# 01_-_Power.net
KiCad netlist of a schematic drawn in Altium Designer
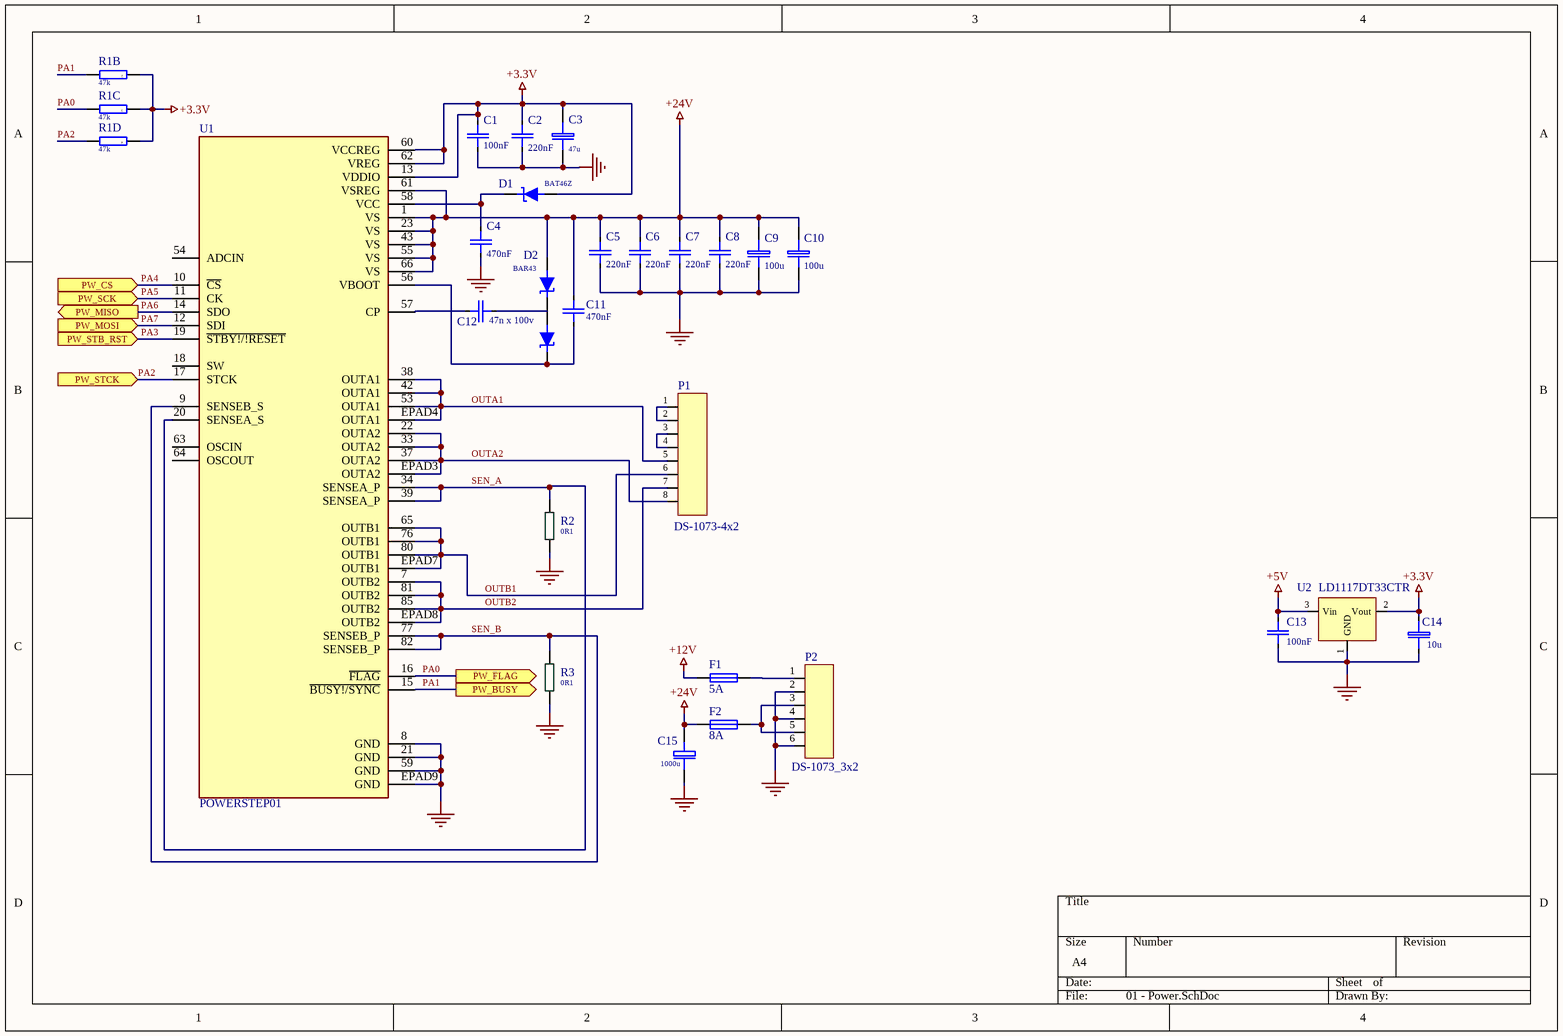
[diagram p0: 01 - Power.SchDoc]

(export (version "E")
  (design (tool "Eeschema 10.0.6"))
  (components
    (comp (ref "C1")
      (value "100nF")
      (footprint "CAP: 0805")
      (description "SMD-0805")
      (libsource (lib "RCL_SMD_Integrated_Library") (part "C-0805"))
    )
    (comp (ref "C2")
      (value "220nF")
      (footprint "CAP: 0805")
      (description "SMD-0805")
      (libsource (lib "RCL_SMD_Integrated_Library") (part "C-0805"))
    )
    (comp (ref "C3")
      (value "47u")
      (footprint "EL SMD Case C D5x5.3 h5.4(0505)")
      (description "EL 50V SMD Case C D5x5.3 h5.4")
      (libsource (lib "SMD-RCL") (part "EL 10u/50V"))
    )
    (comp (ref "C4")
      (value "470nF")
      (footprint "CAP: 0805")
      (description "SMD-0805")
      (libsource (lib "RCL_SMD_Integrated_Library") (part "C-0805"))
    )
    (comp (ref "C5")
      (value "220nF")
      (footprint "CAP: 0805")
      (description "SMD-0805")
      (libsource (lib "RCL_SMD_Integrated_Library") (part "C-0805"))
    )
    (comp (ref "C6")
      (value "220nF")
      (footprint "CAP: 0805")
      (description "SMD-0805")
      (libsource (lib "RCL_SMD_Integrated_Library") (part "C-0805"))
    )
    (comp (ref "C7")
      (value "220nF")
      (footprint "CAP: 0805")
      (description "SMD-0805")
      (libsource (lib "RCL_SMD_Integrated_Library") (part "C-0805"))
    )
    (comp (ref "C8")
      (value "220nF")
      (footprint "CAP: 0805")
      (description "SMD-0805")
      (libsource (lib "RCL_SMD_Integrated_Library") (part "C-0805"))
    )
    (comp (ref "C9")
      (value "100u")
      (footprint "EL SMD Case G D10x10.3 h10.2(1010)")
      (description "EL 35V SMD Case G D10x10.3h10.5")
      (libsource (lib "SMD-RCL") (part "EL 100u/35V"))
    )
    (comp (ref "C10")
      (value "100u")
      (footprint "EL SMD Case G D10x10.3 h10.2(1010)")
      (description "EL 35V SMD Case G D10x10.3h10.5")
      (libsource (lib "SMD-RCL") (part "EL 100u/35V"))
    )
    (comp (ref "C11")
      (value "470nF")
      (footprint "CAP: 0805")
      (description "SMD-0805")
      (libsource (lib "RCL_SMD_Integrated_Library") (part "C-0805"))
    )
    (comp (ref "C12")
      (value "47n x 100v")
      (footprint "CAP: 0805")
      (description "SMD-0805")
      (libsource (lib "RCL_SMD_Integrated_Library") (part "C-0805"))
    )
    (comp (ref "C13")
      (value "100nF")
      (footprint "CAP: 0805")
      (description "SMD-0805")
      (libsource (lib "RCL_SMD_Integrated_Library") (part "C-0805"))
    )
    (comp (ref "C14")
      (value "10u")
      (footprint "EL Case A (3216-18)")
      (description "El Case A (2012-12)")
      (libsource (lib "RCL_SMD_Integrated_Library") (part "EL 10u/16V Tant."))
    )
    (comp (ref "C15")
      (value "1000u")
      (footprint "El-d13-h21-F5.08")
      (description "35V 105C 34m 1.8A 5000h")
      (libsource (lib "Cap-El") (part "1000u-35V 105F"))
    )
    (comp (ref "D1")
      (value "BAT46Z")
      (footprint "SOD123")
      (description "SMD-SOT123 60V 15mA 2.2pF 1nS")
      (libsource (lib "Diodes") (part "1N6263"))
    )
    (comp (ref "D2")
      (value "BAR43")
      (footprint "SOT23")
      (description "SMD-SOT23 30V 0.2A 5nS 10pF")
      (libsource (lib "Diodes") (part "BAT54S"))
    )
    (comp (ref "F1")
      (value "5A")
      (footprint "Littelfuse 0451/453")
      (description "0451003")
      (libsource (lib "stm32_Integrated_Library") (part "Littelfuse 0451"))
    )
    (comp (ref "F2")
      (value "8A")
      (footprint "Littelfuse 0451/453")
      (description "0451003")
      (libsource (lib "stm32_Integrated_Library") (part "Littelfuse 0451"))
    )
    (comp (ref "P1")
      (value "DS-1073-4x2")
      (footprint "DS-1073-4x2")
      (libsource (lib "stm32_Integrated_Library") (part "DS-1073-4x2"))
    )
    (comp (ref "P2")
      (value "DS-1073_3x2")
      (footprint "DS-1073-2x3")
      (libsource (lib "stm32_Integrated_Library") (part "DS-1073_3x2"))
    )
    (comp (ref "R1")
      (value "47k")
      (footprint "RM4x0603")
      (description "SMD 4RM-0603 1\\16W 5%")
      (libsource (lib "SMD-RCL") (part "4RM-0603"))
    )
    (comp (ref "R2")
      (value "0R1")
      (footprint "R2512")
      (description "SMD 2512 1W 5% 200V")
      (libsource (lib "SMD-RCL") (part "R-2512"))
    )
    (comp (ref "R3")
      (value "0R1")
      (footprint "R2512")
      (description "SMD 2512 1W 5% 200V")
      (libsource (lib "SMD-RCL") (part "R-2512"))
    )
    (comp (ref "U1")
      (value "POWERSTEP01")
      (footprint "POWERSTEP01")
      (description "Bipolar Motor Driver Power MOSFET SPI 89-VFQFPN _11x14_")
      (fields (field (name "MF") "STMicroelectronics"))
      (libsource (lib "stm32_Integrated_Library") (part "POWERSTEP01"))
    )
    (comp (ref "U2")
      (value "LD1117DT33CTR")
      (footprint "DPAK")
      (libsource (lib "stm32_Integrated_Library") (part "LD1117DT33CTR"))
    )
  )
  (nets
    (net (code "1") (name "+3.3V") (class "Default")
      (node (ref "C1") (pin "2") (pinfunction "2_2") (pintype "passive"))
      (node (ref "C14") (pin "1") (pinfunction "1_1") (pintype "passive"))
      (node (ref "C2") (pin "1") (pinfunction "1_1") (pintype "passive"))
      (node (ref "C3") (pin "1") (pinfunction "+_1") (pintype "passive"))
      (node (ref "D1") (pin "1") (pinfunction "A_1") (pintype "passive"))
      (node (ref "R1") (pin "2") (pinfunction "2_2") (pintype "passive"))
      (node (ref "R1") (pin "3") (pinfunction "3_3") (pintype "passive"))
      (node (ref "R1") (pin "4") (pinfunction "4_4") (pintype "passive"))
      (node (ref "U1") (pin "13") (pinfunction "VDDIO_13") (pintype "power_in"))
      (node (ref "U1") (pin "60") (pinfunction "VCCREG_60") (pintype "power_in"))
      (node (ref "U1") (pin "62") (pinfunction "VREG_62") (pintype "power_in"))
      (node (ref "U2") (pin "2") (pinfunction "Vout_2") (pintype "passive"))
    )
    (net (code "2") (name "+5V") (class "Default")
      (node (ref "C13") (pin "2") (pinfunction "2_2") (pintype "passive"))
      (node (ref "U2") (pin "3") (pinfunction "Vin_3") (pintype "passive"))
    )
    (net (code "3") (name "+12V") (class "Default")
      (node (ref "F1") (pin "1") (pinfunction "1_1") (pintype "passive"))
    )
    (net (code "4") (name "+24V") (class "Default")
      (node (ref "C10") (pin "1") (pinfunction "1_1") (pintype "passive"))
      (node (ref "C11") (pin "1") (pinfunction "1_1") (pintype "passive"))
      (node (ref "C15") (pin "1") (pinfunction "1_1") (pintype "passive"))
      (node (ref "C5") (pin "1") (pinfunction "1_1") (pintype "passive"))
      (node (ref "C6") (pin "1") (pinfunction "1_1") (pintype "passive"))
      (node (ref "C7") (pin "1") (pinfunction "1_1") (pintype "passive"))
      (node (ref "C8") (pin "1") (pinfunction "1_1") (pintype "passive"))
      (node (ref "C9") (pin "1") (pinfunction "1_1") (pintype "passive"))
      (node (ref "D2") (pin "1") (pinfunction "1_1") (pintype "passive"))
      (node (ref "F2") (pin "1") (pinfunction "1_1") (pintype "passive"))
      (node (ref "U1") (pin "1") (pinfunction "VS_1") (pintype "passive"))
      (node (ref "U1") (pin "23") (pinfunction "VS_23") (pintype "passive"))
      (node (ref "U1") (pin "43") (pinfunction "VS_43") (pintype "passive"))
      (node (ref "U1") (pin "55") (pinfunction "VS_55") (pintype "passive"))
      (node (ref "U1") (pin "61") (pinfunction "VSREG_61") (pintype "passive"))
      (node (ref "U1") (pin "66") (pinfunction "VS_66") (pintype "passive"))
    )
    (net (code "5") (name "/OUTA1") (class "Default")
      (node (ref "P1") (pin "5") (pintype "passive"))
      (node (ref "U1") (pin "38") (pinfunction "OUTA1_38") (pintype "power_in"))
      (node (ref "U1") (pin "42") (pinfunction "OUTA1_42") (pintype "power_in"))
      (node (ref "U1") (pin "53") (pinfunction "OUTA1_53") (pintype "power_in"))
      (node (ref "U1") (pin "EPAD4") (pinfunction "OUTA1_EPAD4") (pintype "power_in"))
    )
    (net (code "6") (name "/OUTA2") (class "Default")
      (node (ref "P1") (pin "8") (pintype "passive"))
      (node (ref "U1") (pin "22") (pinfunction "OUTA2_22") (pintype "power_in"))
      (node (ref "U1") (pin "33") (pinfunction "OUTA2_33") (pintype "power_in"))
      (node (ref "U1") (pin "37") (pinfunction "OUTA2_37") (pintype "power_in"))
      (node (ref "U1") (pin "EPAD3") (pinfunction "OUTA2_EPAD3") (pintype "power_in"))
    )
    (net (code "7") (name "/OUTB1") (class "Default")
      (node (ref "P1") (pin "6") (pintype "passive"))
      (node (ref "U1") (pin "65") (pinfunction "OUTB1_65") (pintype "power_in"))
      (node (ref "U1") (pin "76") (pinfunction "OUTB1_76") (pintype "power_in"))
      (node (ref "U1") (pin "80") (pinfunction "OUTB1_80") (pintype "power_in"))
      (node (ref "U1") (pin "EPAD7") (pinfunction "OUTB1_EPAD7") (pintype "power_in"))
    )
    (net (code "8") (name "/OUTB2") (class "Default")
      (node (ref "P1") (pin "7") (pintype "passive"))
      (node (ref "U1") (pin "7") (pinfunction "OUTB2_7") (pintype "power_in"))
      (node (ref "U1") (pin "81") (pinfunction "OUTB2_81") (pintype "power_in"))
      (node (ref "U1") (pin "85") (pinfunction "OUTB2_85") (pintype "power_in"))
      (node (ref "U1") (pin "EPAD8") (pinfunction "OUTB2_EPAD8") (pintype "power_in"))
    )
    (net (code "9") (name "/PA0") (class "Default")
      (node (ref "R1") (pin "6") (pinfunction "6_6") (pintype "passive"))
      (node (ref "U1") (pin "16") (pinfunction "~{FLAG}_16") (pintype "passive"))
    )
    (net (code "10") (name "/PA1") (class "Default")
      (node (ref "R1") (pin "7") (pinfunction "7_7") (pintype "passive"))
      (node (ref "U1") (pin "15") (pinfunction "~{BUSY!/SYNC}_15") (pintype "passive"))
    )
    (net (code "11") (name "/PA2") (class "Default")
      (node (ref "R1") (pin "5") (pinfunction "5_5") (pintype "passive"))
      (node (ref "U1") (pin "17") (pinfunction "STCK_17") (pintype "passive"))
    )
    (net (code "12") (name "/PA3") (class "Default")
      (node (ref "U1") (pin "19") (pinfunction "~{STBY!/!RESET}_19") (pintype "passive"))
    )
    (net (code "13") (name "/PA4") (class "Default")
      (node (ref "U1") (pin "10") (pinfunction "~{CS}_10") (pintype "passive"))
    )
    (net (code "14") (name "/PA5") (class "Default")
      (node (ref "U1") (pin "11") (pinfunction "CK_11") (pintype "passive"))
    )
    (net (code "15") (name "/PA6") (class "Default")
      (node (ref "U1") (pin "14") (pinfunction "SDO_14") (pintype "passive"))
    )
    (net (code "16") (name "/PA7") (class "Default")
      (node (ref "U1") (pin "12") (pinfunction "SDI_12") (pintype "passive"))
    )
    (net (code "17") (name "/SEN_A") (class "Default")
      (node (ref "R2") (pin "2") (pinfunction "2_2") (pintype "passive"))
      (node (ref "U1") (pin "20") (pinfunction "SENSEA_S_20") (pintype "passive"))
      (node (ref "U1") (pin "34") (pinfunction "SENSEA_P_34") (pintype "passive"))
      (node (ref "U1") (pin "39") (pinfunction "SENSEA_P_39") (pintype "passive"))
    )
    (net (code "18") (name "/SEN_B") (class "Default")
      (node (ref "R3") (pin "2") (pinfunction "2_2") (pintype "passive"))
      (node (ref "U1") (pin "77") (pinfunction "SENSEB_P_77") (pintype "passive"))
      (node (ref "U1") (pin "82") (pinfunction "SENSEB_P_82") (pintype "passive"))
      (node (ref "U1") (pin "9") (pinfunction "SENSEB_S_9") (pintype "passive"))
    )
    (net (code "19") (name "GND") (class "Default")
      (node (ref "C1") (pin "1") (pinfunction "1_1") (pintype "passive"))
      (node (ref "C10") (pin "2") (pinfunction "2_2") (pintype "passive"))
      (node (ref "C13") (pin "1") (pinfunction "1_1") (pintype "passive"))
      (node (ref "C14") (pin "2") (pinfunction "2_2") (pintype "passive"))
      (node (ref "C15") (pin "2") (pinfunction "2_2") (pintype "passive"))
      (node (ref "C2") (pin "2") (pinfunction "2_2") (pintype "passive"))
      (node (ref "C3") (pin "2") (pinfunction "-_2") (pintype "passive"))
      (node (ref "C4") (pin "2") (pinfunction "2_2") (pintype "passive"))
      (node (ref "C5") (pin "2") (pinfunction "2_2") (pintype "passive"))
      (node (ref "C6") (pin "2") (pinfunction "2_2") (pintype "passive"))
      (node (ref "C7") (pin "2") (pinfunction "2_2") (pintype "passive"))
      (node (ref "C8") (pin "2") (pinfunction "2_2") (pintype "passive"))
      (node (ref "C9") (pin "2") (pinfunction "2_2") (pintype "passive"))
      (node (ref "P2") (pin "2") (pintype "passive"))
      (node (ref "P2") (pin "4") (pintype "passive"))
      (node (ref "P2") (pin "6") (pintype "passive"))
      (node (ref "R2") (pin "1") (pinfunction "1_1") (pintype "passive"))
      (node (ref "R3") (pin "1") (pinfunction "1_1") (pintype "passive"))
      (node (ref "U1") (pin "21") (pinfunction "GND_21") (pintype "power_in"))
      (node (ref "U1") (pin "59") (pinfunction "GND_59") (pintype "power_in"))
      (node (ref "U1") (pin "8") (pinfunction "GND_8") (pintype "power_in"))
      (node (ref "U1") (pin "EPAD9") (pinfunction "GND_EPAD9") (pintype "power_in"))
      (node (ref "U2") (pin "1") (pinfunction "GND_1") (pintype "passive"))
    )
    (net (code "20") (name "Net-(C12-Pad2)") (class "Default")
      (node (ref "C12") (pin "2") (pinfunction "2_2") (pintype "passive"))
      (node (ref "D2") (pin "3") (pinfunction "3_3") (pintype "passive"))
    )
    (net (code "21") (name "Net-(D1-C)") (class "Default")
      (node (ref "C4") (pin "1") (pinfunction "1_1") (pintype "passive"))
      (node (ref "D1") (pin "2") (pinfunction "C_2") (pintype "passive"))
      (node (ref "U1") (pin "58") (pinfunction "VCC_58") (pintype "power_in"))
    )
    (net (code "22") (name "Net-(F1-Pad2)") (class "Default")
      (node (ref "F1") (pin "2") (pinfunction "2_2") (pintype "passive"))
      (node (ref "P2") (pin "1") (pintype "passive"))
    )
    (net (code "23") (name "Net-(F2-Pad2)") (class "Default")
      (node (ref "F2") (pin "2") (pinfunction "2_2") (pintype "passive"))
      (node (ref "P2") (pin "3") (pintype "passive"))
      (node (ref "P2") (pin "5") (pintype "passive"))
    )
    (net (code "24") (name "Net-(P1-Pad1)") (class "Default")
      (node (ref "P1") (pin "1") (pintype "passive"))
      (node (ref "P1") (pin "2") (pintype "passive"))
    )
    (net (code "25") (name "Net-(P1-Pad3)") (class "Default")
      (node (ref "P1") (pin "3") (pintype "passive"))
      (node (ref "P1") (pin "4") (pintype "passive"))
    )
    (net (code "26") (name "Net-(U1-CP)") (class "Default")
      (node (ref "C12") (pin "1") (pinfunction "1_1") (pintype "passive"))
      (node (ref "U1") (pin "57") (pinfunction "CP_57") (pintype "passive"))
    )
    (net (code "27") (name "Net-(U1-VBOOT)") (class "Default")
      (node (ref "C11") (pin "2") (pinfunction "2_2") (pintype "passive"))
      (node (ref "D2") (pin "2") (pinfunction "2_2") (pintype "passive"))
      (node (ref "U1") (pin "56") (pinfunction "VBOOT_56") (pintype "power_in"))
    )
    (net (code "28") (name "unconnected-(U1-ADCIN-Pad54)") (class "Default")
      (node (ref "U1") (pin "54") (pinfunction "ADCIN_54") (pintype "passive"))
    )
    (net (code "29") (name "unconnected-(U1-OSCIN-Pad63)") (class "Default")
      (node (ref "U1") (pin "63") (pinfunction "OSCIN_63") (pintype "passive"))
    )
    (net (code "30") (name "unconnected-(U1-OSCOUT-Pad64)") (class "Default")
      (node (ref "U1") (pin "64") (pinfunction "OSCOUT_64") (pintype "passive"))
    )
    (net (code "31") (name "unconnected-(U1-SW-Pad18)") (class "Default")
      (node (ref "U1") (pin "18") (pinfunction "SW_18") (pintype "passive"))
    )
  )
)
